# PX4FMUv2_4_6_05.net
KiCad netlist of a schematic drawn in Altium Designer
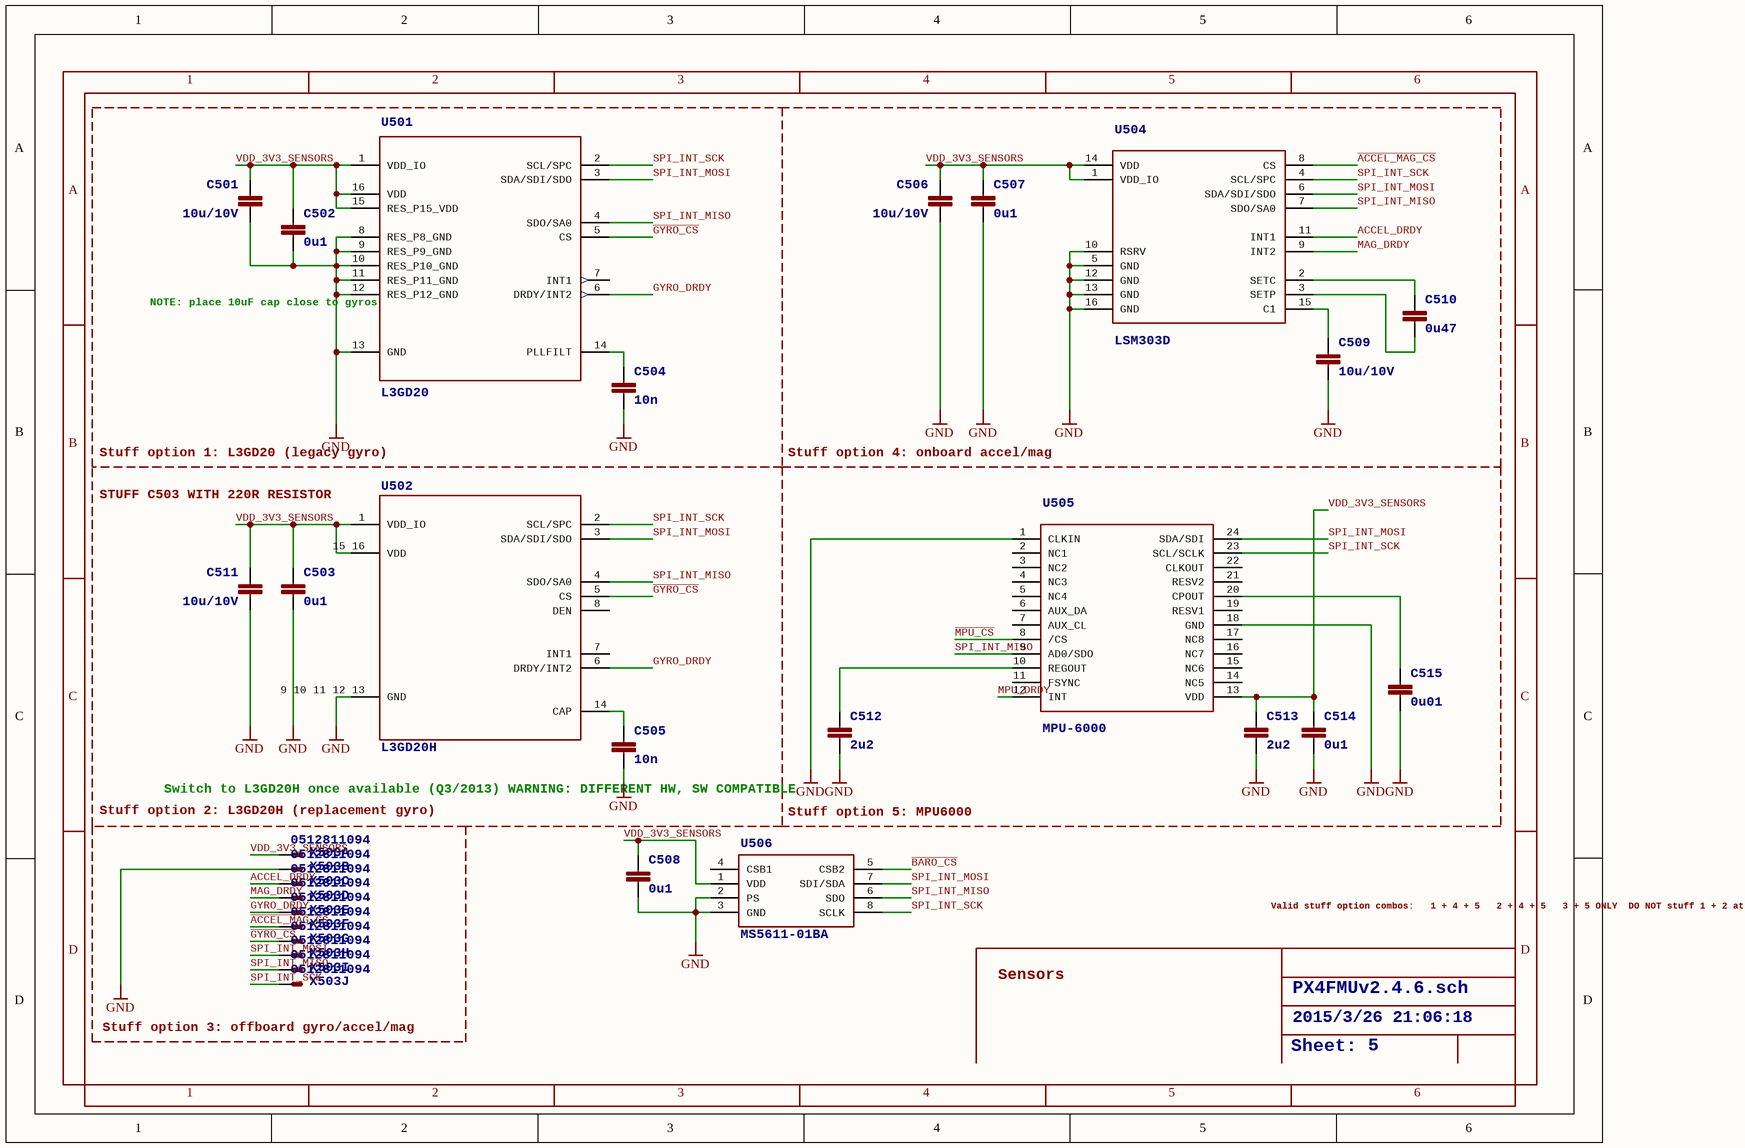
[diagram p0: PX4FMUv2.4.6_05.SchDoc]

(export (version "E")
  (design (tool "Eeschema 10.0.6"))
  (components
    (comp (ref "C501")
      (value "10u/10V")
      (footprint "0805-CAP")
      (description "<b>Capacitor</b>\nStandard 0603 ceramic capacitor, and 0.1\" leaded capacitor.")
      (fields (field (name "PARTNO") "CC0805ZKY5V6BB106"))
      (libsource (lib "pixhawk2") (part "CAP0805"))
    )
    (comp (ref "C502")
      (value "0u1")
      (footprint "0402-CAP")
      (description "<b>Capacitor</b>\nStandard 0603 ceramic capacitor, and 0.1\" leaded capacitor.")
      (fields (field (name "PARTNO") "CC0402ZRY5V7BB104"))
      (libsource (lib "pixhawk2") (part "CAP0402"))
    )
    (comp (ref "C503")
      (value "0u1")
      (footprint "0402-CAP")
      (description "<b>Capacitor</b>\nStandard 0603 ceramic capacitor, and 0.1\" leaded capacitor.")
      (fields (field (name "PARTNO") "CC0402ZRY5V7BB104"))
      (libsource (lib "pixhawk2") (part "CAP0402"))
    )
    (comp (ref "C504")
      (value "10n")
      (footprint "0402-CAP")
      (description "<b>Capacitor</b>\nStandard 0603 ceramic capacitor, and 0.1\" leaded capacitor.")
      (fields (field (name "PARTNO") "CC0402KRX7R7BB103"))
      (libsource (lib "pixhawk2") (part "CAP0402"))
    )
    (comp (ref "C505")
      (value "10n")
      (footprint "0402-CAP")
      (description "<b>Capacitor</b>\nStandard 0603 ceramic capacitor, and 0.1\" leaded capacitor.")
      (fields (field (name "PARTNO") "CC0402KRX7R7BB103"))
      (libsource (lib "pixhawk2") (part "CAP0402"))
    )
    (comp (ref "C506")
      (value "10u/10V")
      (footprint "0805-CAP")
      (description "<b>Capacitor</b>\nStandard 0603 ceramic capacitor, and 0.1\" leaded capacitor.")
      (fields (field (name "PARTNO") "CC0805ZKY5V6BB106"))
      (libsource (lib "pixhawk2") (part "CAP0805"))
    )
    (comp (ref "C507")
      (value "0u1")
      (footprint "0402-CAP")
      (description "<b>Capacitor</b>\nStandard 0603 ceramic capacitor, and 0.1\" leaded capacitor.")
      (fields (field (name "PARTNO") "CC0402ZRY5V7BB104"))
      (libsource (lib "pixhawk2") (part "CAP0402"))
    )
    (comp (ref "C508")
      (value "0u1")
      (footprint "0402-CAP")
      (description "<b>Capacitor</b>\nStandard 0603 ceramic capacitor, and 0.1\" leaded capacitor.")
      (fields (field (name "PARTNO") "CC0402ZRY5V7BB104"))
      (libsource (lib "pixhawk2") (part "CAP0402"))
    )
    (comp (ref "C509")
      (value "10u/10V")
      (footprint "0805-CAP")
      (description "<b>Capacitor</b>\nStandard 0603 ceramic capacitor, and 0.1\" leaded capacitor.")
      (fields (field (name "PARTNO") "CC0805ZKY5V6BB106"))
      (libsource (lib "") (part "CAP0805_1"))
    )
    (comp (ref "C510")
      (value "0u47")
      (footprint "0402-CAP")
      (description "<b>Capacitor</b>\nStandard 0603 ceramic capacitor, and 0.1\" leaded capacitor.")
      (fields (field (name "PARTNO") "C1005X5R1C474K050BC"))
      (libsource (lib "pixhawk2") (part "CAP0402"))
    )
    (comp (ref "C511")
      (value "10u/10V")
      (footprint "0805-CAP")
      (description "<b>Capacitor</b>\nStandard 0603 ceramic capacitor, and 0.1\" leaded capacitor.")
      (fields (field (name "PARTNO") "CC0805ZKY5V6BB106"))
      (libsource (lib "pixhawk2") (part "CAP0805"))
    )
    (comp (ref "C512")
      (value "2u2")
      (footprint "0603-CAP")
      (description "<b>Capacitor</b>\nStandard 0603 ceramic capacitor, and 0.1\" leaded capacitor.")
      (fields (field (name "PARTNO") "C1608X6S1C225K080AC"))
      (libsource (lib "pixhawk2") (part "CAP0603"))
    )
    (comp (ref "C513")
      (value "2u2")
      (footprint "0603-CAP")
      (description "<b>Capacitor</b>\nStandard 0603 ceramic capacitor, and 0.1\" leaded capacitor.")
      (fields (field (name "PARTNO") "C1608X6S1C225K080AC"))
      (libsource (lib "pixhawk2") (part "CAP0603"))
    )
    (comp (ref "C514")
      (value "0u1")
      (footprint "0402-CAP")
      (description "<b>Capacitor</b>\nStandard 0603 ceramic capacitor, and 0.1\" leaded capacitor.")
      (fields (field (name "PARTNO") "CC0402ZRY5V7BB104"))
      (libsource (lib "pixhawk2") (part "CAP0402"))
    )
    (comp (ref "C515")
      (value "0u01")
      (footprint "0603-CAP")
      (description "<b>Capacitor</b>\nStandard 0603 ceramic capacitor, and 0.1\" leaded capacitor.")
      (fields (field (name "PARTNO") "06033C103JAT2A"))
      (libsource (lib "pixhawk2") (part "CAP0603"))
    )
    (comp (ref "U501")
      (value "L3GD20")
      (footprint "L3G4200DH-MAN")
      (libsource (lib "pixhawk2") (part "L3G4200DH-LL"))
    )
    (comp (ref "U502")
      (value "L3GD20H")
      (footprint "LGA-16L")
      (description "<b>L3GD20H MEMS motion sensor: 3-axis digital output gyroscope</b>")
      (libsource (lib "pixhawk2") (part "L3GD20H"))
    )
    (comp (ref "U504") (value "LSM303D") (footprint "LGA-16L") (libsource (lib "pixhawk2") (part "LSM303D")))
    (comp (ref "U505") (value "MPU-6000") (footprint "QFN-24") (libsource (lib "pixhawk2") (part "MPU-6000")))
    (comp (ref "U506")
      (value "MS5611-01BA")
      (footprint "MS5611-01BA")
      (libsource (lib "pixhawk2") (part "MS5611-01BA"))
    )
    (comp (ref "X503")
      (value "0512811094")
      (footprint "51281-1094")
      (description "10-pin FPC connector for PX4 sensor board")
      (fields (field (name "PARTNO") "0781191109"))
      (libsource (lib "pixhawk2") (part "CONN_FPC_10RA"))
    )
  )
  (nets
    (net (code "1") (name "/ACCEL_DRDY") (class "Default")
      (node (ref "U504") (pin "11") (pinfunction "INT1_11") (pintype "passive"))
      (node (ref "X503") (pin "3") (pinfunction "S_3") (pintype "passive"))
    )
    (net (code "2") (name "/GYRO_DRDY") (class "Default")
      (node (ref "U501") (pin "6") (pinfunction "DRDY/INT2_6") (pintype "output"))
      (node (ref "U502") (pin "6") (pinfunction "DRDY/INT2_6") (pintype "passive"))
      (node (ref "X503") (pin "5") (pinfunction "S_5") (pintype "passive"))
    )
    (net (code "3") (name "/MAG_DRDY") (class "Default")
      (node (ref "U504") (pin "9") (pinfunction "INT2_9") (pintype "passive"))
      (node (ref "X503") (pin "4") (pinfunction "S_4") (pintype "passive"))
    )
    (net (code "4") (name "/MPU_DRDY") (class "Default")
      (node (ref "U505") (pin "12") (pinfunction "INT_12") (pintype "passive"))
    )
    (net (code "5") (name "/SPI_INT_MISO") (class "Default")
      (node (ref "U501") (pin "4") (pinfunction "SDO/SA0_4") (pintype "passive"))
      (node (ref "U502") (pin "4") (pinfunction "SDO/SA0_4") (pintype "passive"))
      (node (ref "U504") (pin "7") (pinfunction "SDO/SA0_7") (pintype "passive"))
      (node (ref "U505") (pin "9") (pinfunction "AD0/SDO_9") (pintype "passive"))
      (node (ref "U506") (pin "6") (pinfunction "SDO_6") (pintype "passive"))
      (node (ref "X503") (pin "9") (pinfunction "S_9") (pintype "passive"))
    )
    (net (code "6") (name "/SPI_INT_MOSI") (class "Default")
      (node (ref "U501") (pin "3") (pinfunction "SDA/SDI/SDO_3") (pintype "passive"))
      (node (ref "U502") (pin "3") (pinfunction "SDA/SDI/SDO_3") (pintype "passive"))
      (node (ref "U504") (pin "6") (pinfunction "SDA/SDI/SDO_6") (pintype "passive"))
      (node (ref "U505") (pin "24") (pinfunction "SDA/SDI_24") (pintype "passive"))
      (node (ref "U506") (pin "7") (pinfunction "SDI/SDA_7") (pintype "passive"))
      (node (ref "X503") (pin "8") (pinfunction "S_8") (pintype "passive"))
    )
    (net (code "7") (name "/SPI_INT_SCK") (class "Default")
      (node (ref "U501") (pin "2") (pinfunction "SCL/SPC_2") (pintype "passive"))
      (node (ref "U502") (pin "2") (pinfunction "SCL/SPC_2") (pintype "passive"))
      (node (ref "U504") (pin "4") (pinfunction "SCL/SPC_4") (pintype "passive"))
      (node (ref "U505") (pin "23") (pinfunction "SCL/SCLK_23") (pintype "passive"))
      (node (ref "U506") (pin "8") (pinfunction "SCLK_8") (pintype "passive"))
      (node (ref "X503") (pin "10") (pinfunction "S_10") (pintype "passive"))
    )
    (net (code "8") (name "/VDD_3V3_SENSORS") (class "Default")
      (node (ref "C501") (pin "P$1") (pinfunction "1_P$1") (pintype "passive"))
      (node (ref "C502") (pin "P$1") (pinfunction "1_P$1") (pintype "passive"))
      (node (ref "C503") (pin "P$1") (pinfunction "1_P$1") (pintype "passive"))
      (node (ref "C506") (pin "P$1") (pinfunction "1_P$1") (pintype "passive"))
      (node (ref "C507") (pin "P$1") (pinfunction "1_P$1") (pintype "passive"))
      (node (ref "C508") (pin "P$1") (pinfunction "1_P$1") (pintype "passive"))
      (node (ref "C511") (pin "P$1") (pinfunction "1_P$1") (pintype "passive"))
      (node (ref "C513") (pin "P$1") (pinfunction "1_P$1") (pintype "passive"))
      (node (ref "C514") (pin "P$1") (pinfunction "1_P$1") (pintype "passive"))
      (node (ref "U501") (pin "1") (pinfunction "VDD_IO_1") (pintype "passive"))
      (node (ref "U501") (pin "15") (pinfunction "RES_P15_VDD_15") (pintype "passive"))
      (node (ref "U501") (pin "16") (pinfunction "VDD_16") (pintype "passive"))
      (node (ref "U502") (pin "1") (pinfunction "VDD_IO_1") (pintype "passive"))
      (node (ref "U502") (pin "15_16") (pinfunction "VDD_15_16") (pintype "passive"))
      (node (ref "U504") (pin "1") (pinfunction "VDD_IO_1") (pintype "passive"))
      (node (ref "U504") (pin "14") (pinfunction "VDD_14") (pintype "passive"))
      (node (ref "U505") (pin "13") (pinfunction "VDD_13") (pintype "passive"))
      (node (ref "U506") (pin "1") (pinfunction "VDD_1") (pintype "passive"))
      (node (ref "X503") (pin "1") (pinfunction "S_1") (pintype "passive"))
    )
    (net (code "9") (name "/~{ACCEL_MAG_CS}") (class "Default")
      (node (ref "U504") (pin "8") (pinfunction "CS_8") (pintype "passive"))
      (node (ref "X503") (pin "6") (pinfunction "S_6") (pintype "passive"))
    )
    (net (code "10") (name "/~{BARO_CS}") (class "Default")
      (node (ref "U506") (pin "5") (pinfunction "CSB2_5") (pintype "passive"))
    )
    (net (code "11") (name "/~{GYRO_CS}") (class "Default")
      (node (ref "U501") (pin "5") (pinfunction "CS_5") (pintype "passive"))
      (node (ref "U502") (pin "5") (pinfunction "CS_5") (pintype "passive"))
      (node (ref "X503") (pin "7") (pinfunction "S_7") (pintype "passive"))
    )
    (net (code "12") (name "/~{MPU_CS}") (class "Default")
      (node (ref "U505") (pin "8") (pinfunction "/CS_8") (pintype "passive"))
    )
    (net (code "13") (name "GND") (class "Default")
      (node (ref "C501") (pin "P$2") (pinfunction "2_P$2") (pintype "passive"))
      (node (ref "C502") (pin "P$2") (pinfunction "2_P$2") (pintype "passive"))
      (node (ref "C503") (pin "P$2") (pinfunction "2_P$2") (pintype "passive"))
      (node (ref "C504") (pin "P$2") (pinfunction "2_P$2") (pintype "passive"))
      (node (ref "C505") (pin "P$2") (pinfunction "2_P$2") (pintype "passive"))
      (node (ref "C506") (pin "P$2") (pinfunction "2_P$2") (pintype "passive"))
      (node (ref "C507") (pin "P$2") (pinfunction "2_P$2") (pintype "passive"))
      (node (ref "C508") (pin "P$2") (pinfunction "2_P$2") (pintype "passive"))
      (node (ref "C509") (pin "P$2") (pinfunction "2_P$2") (pintype "passive"))
      (node (ref "C511") (pin "P$2") (pinfunction "2_P$2") (pintype "passive"))
      (node (ref "C512") (pin "P$2") (pinfunction "2_P$2") (pintype "passive"))
      (node (ref "C513") (pin "P$2") (pinfunction "2_P$2") (pintype "passive"))
      (node (ref "C514") (pin "P$2") (pinfunction "2_P$2") (pintype "passive"))
      (node (ref "C515") (pin "P$2") (pinfunction "2_P$2") (pintype "passive"))
      (node (ref "U501") (pin "10") (pinfunction "RES_P10_GND_10") (pintype "passive"))
      (node (ref "U501") (pin "11") (pinfunction "RES_P11_GND_11") (pintype "passive"))
      (node (ref "U501") (pin "12") (pinfunction "RES_P12_GND_12") (pintype "passive"))
      (node (ref "U501") (pin "13") (pinfunction "GND_13") (pintype "passive"))
      (node (ref "U501") (pin "8") (pinfunction "RES_P8_GND_8") (pintype "passive"))
      (node (ref "U501") (pin "9") (pinfunction "RES_P9_GND_9") (pintype "passive"))
      (node (ref "U502") (pin "9_10_11_12_13") (pinfunction "GND_9_10_11_12_13") (pintype "passive"))
      (node (ref "U504") (pin "10") (pinfunction "RSRV_10") (pintype "passive"))
      (node (ref "U504") (pin "12") (pinfunction "GND_12") (pintype "passive"))
      (node (ref "U504") (pin "13") (pinfunction "GND_13") (pintype "passive"))
      (node (ref "U504") (pin "16") (pinfunction "GND_16") (pintype "passive"))
      (node (ref "U504") (pin "5") (pinfunction "GND_5") (pintype "passive"))
      (node (ref "U505") (pin "1") (pinfunction "CLKIN_1") (pintype "passive"))
      (node (ref "U505") (pin "18") (pinfunction "GND_18") (pintype "passive"))
      (node (ref "U506") (pin "2") (pinfunction "PS_2") (pintype "passive"))
      (node (ref "U506") (pin "3") (pinfunction "GND_3") (pintype "passive"))
      (node (ref "X503") (pin "2") (pinfunction "S_2") (pintype "passive"))
    )
    (net (code "14") (name "Net-(C504-1)") (class "Default")
      (node (ref "C504") (pin "P$1") (pinfunction "1_P$1") (pintype "passive"))
      (node (ref "U501") (pin "14") (pinfunction "PLLFILT_14") (pintype "passive"))
    )
    (net (code "15") (name "Net-(C505-1)") (class "Default")
      (node (ref "C505") (pin "P$1") (pinfunction "1_P$1") (pintype "passive"))
      (node (ref "U502") (pin "14") (pinfunction "CAP_14") (pintype "passive"))
    )
    (net (code "16") (name "Net-(C509-1)") (class "Default")
      (node (ref "C509") (pin "P$1") (pinfunction "1_P$1") (pintype "passive"))
      (node (ref "U504") (pin "15") (pinfunction "C1_15") (pintype "passive"))
    )
    (net (code "17") (name "Net-(C510-1)") (class "Default")
      (node (ref "C510") (pin "P$1") (pinfunction "1_P$1") (pintype "passive"))
      (node (ref "U504") (pin "2") (pinfunction "SETC_2") (pintype "passive"))
    )
    (net (code "18") (name "Net-(C510-2)") (class "Default")
      (node (ref "C510") (pin "P$2") (pinfunction "2_P$2") (pintype "passive"))
      (node (ref "U504") (pin "3") (pinfunction "SETP_3") (pintype "passive"))
    )
    (net (code "19") (name "Net-(C512-1)") (class "Default")
      (node (ref "C512") (pin "P$1") (pinfunction "1_P$1") (pintype "passive"))
      (node (ref "U505") (pin "10") (pinfunction "REGOUT_10") (pintype "passive"))
    )
    (net (code "20") (name "Net-(C515-1)") (class "Default")
      (node (ref "C515") (pin "P$1") (pinfunction "1_P$1") (pintype "passive"))
      (node (ref "U505") (pin "20") (pinfunction "CPOUT_20") (pintype "passive"))
    )
    (net (code "21") (name "unconnected-(U501-INT1-Pad7)") (class "Default")
      (node (ref "U501") (pin "7") (pinfunction "INT1_7") (pintype "output"))
    )
    (net (code "22") (name "unconnected-(U502-DEN-Pad8)") (class "Default")
      (node (ref "U502") (pin "8") (pinfunction "DEN_8") (pintype "passive"))
    )
    (net (code "23") (name "unconnected-(U502-INT1-Pad7)") (class "Default")
      (node (ref "U502") (pin "7") (pinfunction "INT1_7") (pintype "passive"))
    )
    (net (code "24") (name "unconnected-(U505-AUX_CL-Pad7)") (class "Default")
      (node (ref "U505") (pin "7") (pinfunction "AUX_CL_7") (pintype "passive"))
    )
    (net (code "25") (name "unconnected-(U505-AUX_DA-Pad6)") (class "Default")
      (node (ref "U505") (pin "6") (pinfunction "AUX_DA_6") (pintype "passive"))
    )
    (net (code "26") (name "unconnected-(U505-CLKOUT-Pad22)") (class "Default")
      (node (ref "U505") (pin "22") (pinfunction "CLKOUT_22") (pintype "passive"))
    )
    (net (code "27") (name "unconnected-(U505-FSYNC-Pad11)") (class "Default")
      (node (ref "U505") (pin "11") (pinfunction "FSYNC_11") (pintype "passive"))
    )
    (net (code "28") (name "unconnected-(U505-NC1-Pad2)") (class "Default")
      (node (ref "U505") (pin "2") (pinfunction "NC1_2") (pintype "passive"))
    )
    (net (code "29") (name "unconnected-(U505-NC2-Pad3)") (class "Default")
      (node (ref "U505") (pin "3") (pinfunction "NC2_3") (pintype "passive"))
    )
    (net (code "30") (name "unconnected-(U505-NC3-Pad4)") (class "Default")
      (node (ref "U505") (pin "4") (pinfunction "NC3_4") (pintype "passive"))
    )
    (net (code "31") (name "unconnected-(U505-NC4-Pad5)") (class "Default")
      (node (ref "U505") (pin "5") (pinfunction "NC4_5") (pintype "passive"))
    )
    (net (code "32") (name "unconnected-(U505-NC5-Pad14)") (class "Default")
      (node (ref "U505") (pin "14") (pinfunction "NC5_14") (pintype "passive"))
    )
    (net (code "33") (name "unconnected-(U505-NC6-Pad15)") (class "Default")
      (node (ref "U505") (pin "15") (pinfunction "NC6_15") (pintype "passive"))
    )
    (net (code "34") (name "unconnected-(U505-NC7-Pad16)") (class "Default")
      (node (ref "U505") (pin "16") (pinfunction "NC7_16") (pintype "passive"))
    )
    (net (code "35") (name "unconnected-(U505-NC8-Pad17)") (class "Default")
      (node (ref "U505") (pin "17") (pinfunction "NC8_17") (pintype "passive"))
    )
    (net (code "36") (name "unconnected-(U505-RESV1-Pad19)") (class "Default")
      (node (ref "U505") (pin "19") (pinfunction "RESV1_19") (pintype "passive"))
    )
    (net (code "37") (name "unconnected-(U505-RESV2-Pad21)") (class "Default")
      (node (ref "U505") (pin "21") (pinfunction "RESV2_21") (pintype "passive"))
    )
    (net (code "38") (name "unconnected-(U506-CSB1-Pad4)") (class "Default")
      (node (ref "U506") (pin "4") (pinfunction "CSB1_4") (pintype "passive"))
    )
  )
)
